# split-supply-2_5.net
KiCad netlist of a schematic drawn in EAGLE
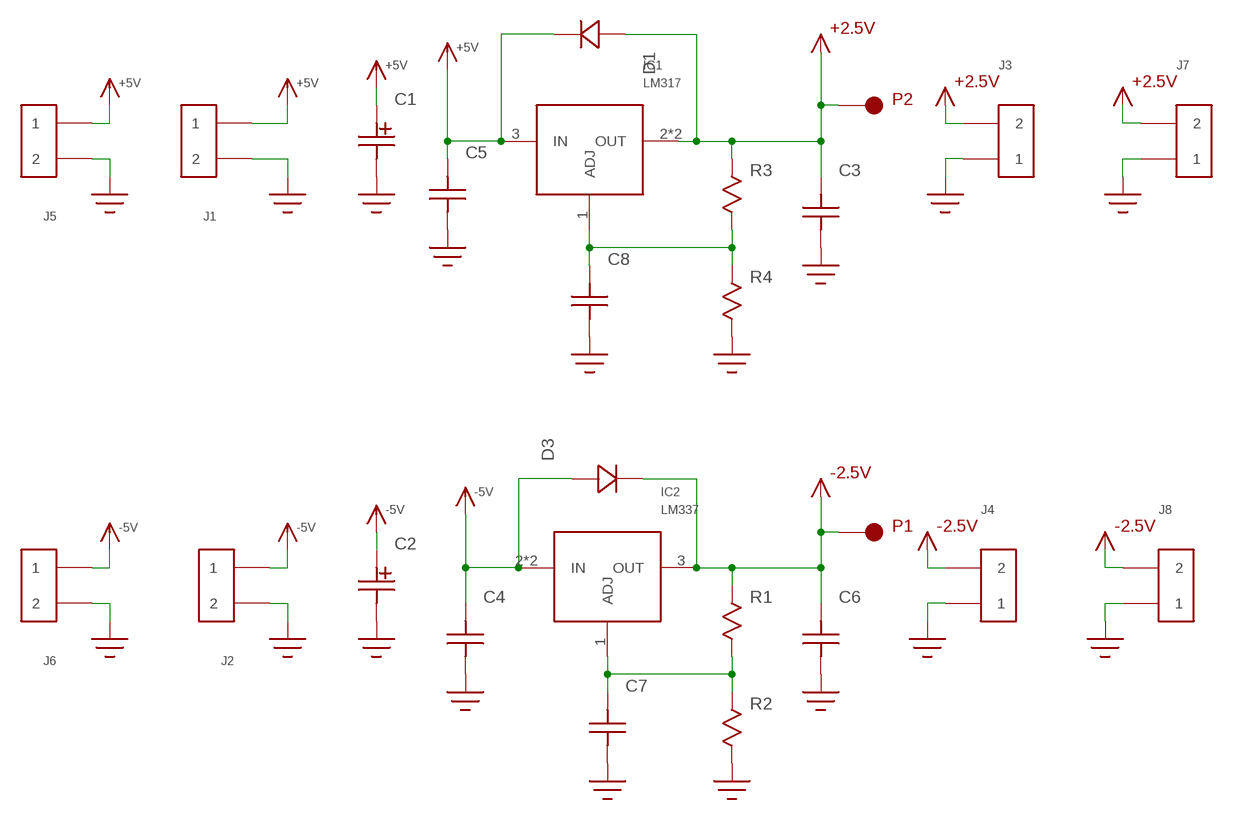
[diagram p0: schematic, sheet 1]

(export (version "E")
  (design (tool "Eeschema 10.0.6"))
  (components
    (comp (ref "C1")
      (value "C-POLARIZED")
      (footprint "eagle-import:CAP-E61")
      (libsource (lib "eagle-import") (part "C-POLARIZED"))
    )
    (comp (ref "C2")
      (value "C-POLARIZED")
      (footprint "eagle-import:CAP-E61")
      (libsource (lib "eagle-import") (part "C-POLARIZED"))
    )
    (comp (ref "C3")
      (value "C1206")
      (footprint "eagle-import:1206")
      (libsource (lib "eagle-import") (part "C1206"))
    )
    (comp (ref "C4")
      (value "C1206")
      (footprint "eagle-import:1206")
      (libsource (lib "eagle-import") (part "C1206"))
    )
    (comp (ref "C5")
      (value "C1206")
      (footprint "eagle-import:1206")
      (libsource (lib "eagle-import") (part "C1206"))
    )
    (comp (ref "C6")
      (value "C1206")
      (footprint "eagle-import:1206")
      (libsource (lib "eagle-import") (part "C1206"))
    )
    (comp (ref "C7")
      (value "C0603")
      (footprint "eagle-import:C0603")
      (libsource (lib "eagle-import") (part "C0603"))
    )
    (comp (ref "C8")
      (value "C0603")
      (footprint "eagle-import:C0603")
      (libsource (lib "eagle-import") (part "C0603"))
    )
    (comp (ref "D1")
      (value "DIODE")
      (footprint "eagle-import:DO-214(SMA)")
      (libsource (lib "eagle-import") (part "DIODE"))
    )
    (comp (ref "D3")
      (value "DIODE")
      (footprint "eagle-import:DO-214(SMA)")
      (libsource (lib "eagle-import") (part "DIODE"))
    )
    (comp (ref "IC1")
      (value "LM317")
      (footprint "eagle-import:SOT-223")
      (libsource (lib "eagle-import") (part "LM317SOT-223"))
    )
    (comp (ref "IC2")
      (value "LM337")
      (footprint "eagle-import:SOT-223")
      (libsource (lib "eagle-import") (part "LM337"))
    )
    (comp (ref "J1")
      (value "HEADER_2PIN")
      (footprint "eagle-import:HEADER_2PIN")
      (libsource (lib "eagle-import") (part "HEADER_2PIN"))
    )
    (comp (ref "J2")
      (value "HEADER_2PIN")
      (footprint "eagle-import:HEADER_2PIN")
      (libsource (lib "eagle-import") (part "HEADER_2PIN"))
    )
    (comp (ref "J3")
      (value "HEADER_2PIN")
      (footprint "eagle-import:HEADER_2PIN")
      (libsource (lib "eagle-import") (part "HEADER_2PIN"))
    )
    (comp (ref "J4")
      (value "HEADER_2PIN")
      (footprint "eagle-import:HEADER_2PIN")
      (libsource (lib "eagle-import") (part "HEADER_2PIN"))
    )
    (comp (ref "J5")
      (value "HEADER_2PINSCREW-TERM")
      (footprint "eagle-import:FCI_20020316_SCREW_TERM_2P")
      (libsource (lib "eagle-import") (part "HEADER_2PINSCREW-TERM"))
    )
    (comp (ref "J6")
      (value "HEADER_2PINSCREW-TERM")
      (footprint "eagle-import:FCI_20020316_SCREW_TERM_2P")
      (libsource (lib "eagle-import") (part "HEADER_2PINSCREW-TERM"))
    )
    (comp (ref "J7")
      (value "HEADER_2PINSCREW-TERM")
      (footprint "eagle-import:FCI_20020316_SCREW_TERM_2P")
      (libsource (lib "eagle-import") (part "HEADER_2PINSCREW-TERM"))
    )
    (comp (ref "J8")
      (value "HEADER_2PINSCREW-TERM")
      (footprint "eagle-import:FCI_20020316_SCREW_TERM_2P")
      (libsource (lib "eagle-import") (part "HEADER_2PINSCREW-TERM"))
    )
    (comp (ref "P1")
      (value "ICSP_PAD")
      (footprint "eagle-import:ICSP_PAD")
      (libsource (lib "eagle-import") (part "ICSP_PAD"))
    )
    (comp (ref "P2")
      (value "ICSP_PAD")
      (footprint "eagle-import:ICSP_PAD")
      (libsource (lib "eagle-import") (part "ICSP_PAD"))
    )
    (comp (ref "R1")
      (value "R0603")
      (footprint "eagle-import:R0603")
      (libsource (lib "eagle-import") (part "R0603"))
    )
    (comp (ref "R2")
      (value "R0603")
      (footprint "eagle-import:R0603")
      (libsource (lib "eagle-import") (part "R0603"))
    )
    (comp (ref "R3")
      (value "R0603")
      (footprint "eagle-import:R0603")
      (libsource (lib "eagle-import") (part "R0603"))
    )
    (comp (ref "R4")
      (value "R0603")
      (footprint "eagle-import:R0603")
      (libsource (lib "eagle-import") (part "R0603"))
    )
  )
  (nets
    (net (code "1") (name "+2.5V") (class "Default")
      (node (ref "C3") (pin "P$2") (pinfunction "P$2_P$2") (pintype "bidirectional"))
      (node (ref "D1") (pin "C") (pinfunction "CATHODE_C") (pintype "bidirectional"))
      (node (ref "IC1") (pin "2") (pinfunction "OUT_2") (pintype "bidirectional"))
      (node (ref "IC1") (pin "4") (pinfunction "OUT_4") (pintype "bidirectional"))
      (node (ref "J3") (pin "2") (pinfunction "2_2") (pintype "bidirectional"))
      (node (ref "J7") (pin "P$2") (pinfunction "2_P$2") (pintype "bidirectional"))
      (node (ref "P2") (pin "P$1") (pinfunction "P$1_P$1") (pintype "bidirectional"))
      (node (ref "R3") (pin "P$1") (pinfunction "P$3_P$1") (pintype "bidirectional"))
    )
    (net (code "2") (name "+5V") (class "Default")
      (node (ref "C1") (pin "+") (pinfunction "+_+") (pintype "bidirectional"))
      (node (ref "C5") (pin "P$2") (pinfunction "P$2_P$2") (pintype "bidirectional"))
      (node (ref "D1") (pin "A") (pinfunction "ANODE_A") (pintype "bidirectional"))
      (node (ref "IC1") (pin "3") (pinfunction "IN_3") (pintype "bidirectional"))
      (node (ref "J1") (pin "1") (pinfunction "1_1") (pintype "bidirectional"))
      (node (ref "J5") (pin "P$1") (pinfunction "1_P$1") (pintype "bidirectional"))
    )
    (net (code "3") (name "-2.5V") (class "Default")
      (node (ref "C6") (pin "P$2") (pinfunction "P$2_P$2") (pintype "bidirectional"))
      (node (ref "D3") (pin "A") (pinfunction "ANODE_A") (pintype "bidirectional"))
      (node (ref "IC2") (pin "3") (pinfunction "OUT_3") (pintype "bidirectional"))
      (node (ref "J4") (pin "2") (pinfunction "2_2") (pintype "bidirectional"))
      (node (ref "J8") (pin "P$2") (pinfunction "2_P$2") (pintype "bidirectional"))
      (node (ref "P1") (pin "P$1") (pinfunction "P$1_P$1") (pintype "bidirectional"))
      (node (ref "R1") (pin "P$1") (pinfunction "P$3_P$1") (pintype "bidirectional"))
    )
    (net (code "4") (name "-5V") (class "Default")
      (node (ref "C2") (pin "+") (pinfunction "+_+") (pintype "bidirectional"))
      (node (ref "C4") (pin "P$2") (pinfunction "P$2_P$2") (pintype "bidirectional"))
      (node (ref "D3") (pin "C") (pinfunction "CATHODE_C") (pintype "bidirectional"))
      (node (ref "IC2") (pin "2") (pinfunction "IN_2") (pintype "bidirectional"))
      (node (ref "IC2") (pin "4") (pinfunction "IN_4") (pintype "bidirectional"))
      (node (ref "J2") (pin "1") (pinfunction "1_1") (pintype "bidirectional"))
      (node (ref "J6") (pin "P$1") (pinfunction "1_P$1") (pintype "bidirectional"))
    )
    (net (code "5") (name "GND") (class "Default")
      (node (ref "C1") (pin "-") (pinfunction "-_-") (pintype "bidirectional"))
      (node (ref "C2") (pin "-") (pinfunction "-_-") (pintype "bidirectional"))
      (node (ref "C3") (pin "P$1") (pinfunction "P$1_P$1") (pintype "bidirectional"))
      (node (ref "C4") (pin "P$1") (pinfunction "P$1_P$1") (pintype "bidirectional"))
      (node (ref "C5") (pin "P$1") (pinfunction "P$1_P$1") (pintype "bidirectional"))
      (node (ref "C6") (pin "P$1") (pinfunction "P$1_P$1") (pintype "bidirectional"))
      (node (ref "C7") (pin "P$1") (pinfunction "P$1_P$1") (pintype "bidirectional"))
      (node (ref "C8") (pin "P$1") (pinfunction "P$1_P$1") (pintype "bidirectional"))
      (node (ref "J1") (pin "2") (pinfunction "2_2") (pintype "bidirectional"))
      (node (ref "J2") (pin "2") (pinfunction "2_2") (pintype "bidirectional"))
      (node (ref "J3") (pin "1") (pinfunction "1_1") (pintype "bidirectional"))
      (node (ref "J4") (pin "1") (pinfunction "1_1") (pintype "bidirectional"))
      (node (ref "J5") (pin "P$2") (pinfunction "2_P$2") (pintype "bidirectional"))
      (node (ref "J6") (pin "P$2") (pinfunction "2_P$2") (pintype "bidirectional"))
      (node (ref "J7") (pin "P$1") (pinfunction "1_P$1") (pintype "bidirectional"))
      (node (ref "J8") (pin "P$1") (pinfunction "1_P$1") (pintype "bidirectional"))
      (node (ref "R2") (pin "P$2") (pinfunction "P$4_P$2") (pintype "bidirectional"))
      (node (ref "R4") (pin "P$2") (pinfunction "P$4_P$2") (pintype "bidirectional"))
    )
    (net (code "6") (name "Net-(IC1-ADJ)") (class "Default")
      (node (ref "C8") (pin "P$2") (pinfunction "P$2_P$2") (pintype "bidirectional"))
      (node (ref "IC1") (pin "1") (pinfunction "ADJ_1") (pintype "bidirectional"))
      (node (ref "R3") (pin "P$2") (pinfunction "P$4_P$2") (pintype "bidirectional"))
      (node (ref "R4") (pin "P$1") (pinfunction "P$3_P$1") (pintype "bidirectional"))
    )
    (net (code "7") (name "Net-(IC2-ADJ)") (class "Default")
      (node (ref "C7") (pin "P$2") (pinfunction "P$2_P$2") (pintype "bidirectional"))
      (node (ref "IC2") (pin "1") (pinfunction "ADJ_1") (pintype "bidirectional"))
      (node (ref "R1") (pin "P$2") (pinfunction "P$4_P$2") (pintype "bidirectional"))
      (node (ref "R2") (pin "P$1") (pinfunction "P$3_P$1") (pintype "bidirectional"))
    )
  )
)
